# USBtoUART.net
KiCad netlist of a schematic drawn in Altium Designer
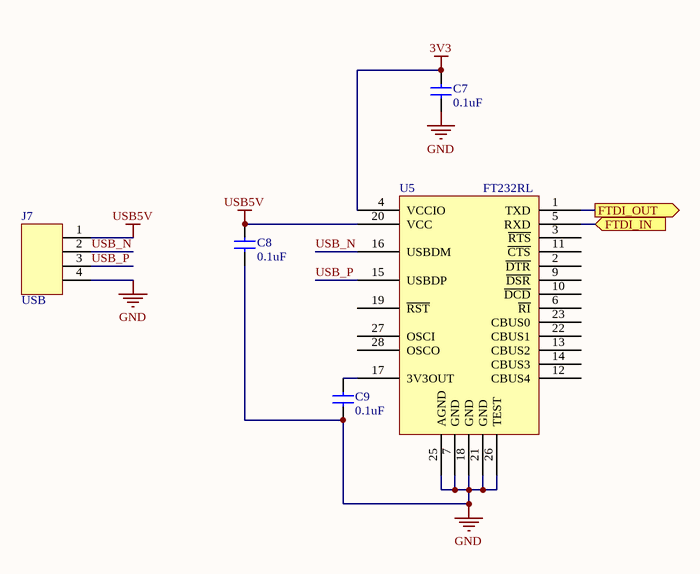
[diagram p0: USBtoUART.SchDoc]

(export (version "E")
  (design (tool "Eeschema 10.0.6"))
  (components
    (comp (ref "C7")
      (value "0.1uF")
      (footprint "CAPC0603")
      (fields (field (name "Comment") "Cap"))
      (libsource (lib "Passives") (part "Cap"))
    )
    (comp (ref "C8")
      (value "0.1uF")
      (footprint "CAPC0603")
      (fields (field (name "Comment") "Cap"))
      (libsource (lib "Passives") (part "Cap"))
    )
    (comp (ref "C9")
      (value "0.1uF")
      (footprint "CAPC0603")
      (fields (field (name "Comment") "Cap"))
      (libsource (lib "Passives") (part "Cap"))
    )
    (comp (ref "J7")
      (value "USB")
      (footprint "MOLEX-HDR-1X4-SHERLOCK-VERT")
      (libsource (lib "Connectors") (part "MOLEX-HDR-1x4-SHERLOCK_VERT"))
    )
    (comp (ref "U5")
      (value "FT232RL")
      (footprint "SSOP_28_N")
      (description "IC USB FS SERIAL UART 28-SSOP")
      (libsource (lib "ICs") (part "FT232RL"))
    )
  )
  (nets
    (net (code "1") (name "/FTDI_IN") (class "Default")
      (node (ref "U5") (pin "5") (pinfunction "RXD_5") (pintype "passive"))
    )
    (net (code "2") (name "/FTDI_OUT") (class "Default")
      (node (ref "U5") (pin "1") (pinfunction "TXD_1") (pintype "passive"))
    )
    (net (code "3") (name "/USB_N") (class "Default")
      (node (ref "J7") (pin "2") (pinfunction "2_2") (pintype "passive"))
      (node (ref "U5") (pin "16") (pinfunction "USBDM_16") (pintype "passive"))
    )
    (net (code "4") (name "/USB_P") (class "Default")
      (node (ref "J7") (pin "3") (pinfunction "3_3") (pintype "passive"))
      (node (ref "U5") (pin "15") (pinfunction "USBDP_15") (pintype "passive"))
    )
    (net (code "5") (name "3V3") (class "Default")
      (node (ref "C7") (pin "1") (pinfunction "A_1") (pintype "passive"))
      (node (ref "U5") (pin "4") (pinfunction "VCCIO_4") (pintype "passive"))
    )
    (net (code "6") (name "GND") (class "Default")
      (node (ref "C7") (pin "2") (pinfunction "B_2") (pintype "passive"))
      (node (ref "C8") (pin "2") (pinfunction "B_2") (pintype "passive"))
      (node (ref "C9") (pin "2") (pinfunction "B_2") (pintype "passive"))
      (node (ref "J7") (pin "4") (pinfunction "4_4") (pintype "passive"))
      (node (ref "U5") (pin "18") (pinfunction "GND_18") (pintype "passive"))
      (node (ref "U5") (pin "21") (pinfunction "GND_21") (pintype "passive"))
      (node (ref "U5") (pin "25") (pinfunction "AGND_25") (pintype "passive"))
      (node (ref "U5") (pin "26") (pinfunction "TEST_26") (pintype "passive"))
      (node (ref "U5") (pin "7") (pinfunction "GND_7") (pintype "passive"))
    )
    (net (code "7") (name "Net-(C9-A)") (class "Default")
      (node (ref "C9") (pin "1") (pinfunction "A_1") (pintype "passive"))
      (node (ref "U5") (pin "17") (pinfunction "3V3OUT_17") (pintype "passive"))
    )
    (net (code "8") (name "USB5V") (class "Default")
      (node (ref "C8") (pin "1") (pinfunction "A_1") (pintype "passive"))
      (node (ref "J7") (pin "1") (pinfunction "1_1") (pintype "passive"))
      (node (ref "U5") (pin "20") (pinfunction "VCC_20") (pintype "passive"))
    )
    (net (code "9") (name "unconnected-(U5-CBUS0-Pad23)") (class "Default")
      (node (ref "U5") (pin "23") (pinfunction "CBUS0_23") (pintype "passive"))
    )
    (net (code "10") (name "unconnected-(U5-CBUS1-Pad22)") (class "Default")
      (node (ref "U5") (pin "22") (pinfunction "CBUS1_22") (pintype "passive"))
    )
    (net (code "11") (name "unconnected-(U5-CBUS2-Pad13)") (class "Default")
      (node (ref "U5") (pin "13") (pinfunction "CBUS2_13") (pintype "passive"))
    )
    (net (code "12") (name "unconnected-(U5-CBUS3-Pad14)") (class "Default")
      (node (ref "U5") (pin "14") (pinfunction "CBUS3_14") (pintype "passive"))
    )
    (net (code "13") (name "unconnected-(U5-CBUS4-Pad12)") (class "Default")
      (node (ref "U5") (pin "12") (pinfunction "CBUS4_12") (pintype "passive"))
    )
    (net (code "14") (name "unconnected-(U5-OSCI-Pad27)") (class "Default")
      (node (ref "U5") (pin "27") (pinfunction "OSCI_27") (pintype "passive"))
    )
    (net (code "15") (name "unconnected-(U5-OSCO-Pad28)") (class "Default")
      (node (ref "U5") (pin "28") (pinfunction "OSCO_28") (pintype "passive"))
    )
    (net (code "16") (name "unconnected-(U5-~{CTS}-Pad11)") (class "Default")
      (node (ref "U5") (pin "11") (pinfunction "~{CTS}_11") (pintype "passive"))
    )
    (net (code "17") (name "unconnected-(U5-~{DCD}-Pad10)") (class "Default")
      (node (ref "U5") (pin "10") (pinfunction "~{DCD}_10") (pintype "passive"))
    )
    (net (code "18") (name "unconnected-(U5-~{DSR}-Pad9)") (class "Default")
      (node (ref "U5") (pin "9") (pinfunction "~{DSR}_9") (pintype "passive"))
    )
    (net (code "19") (name "unconnected-(U5-~{DTR}-Pad2)") (class "Default")
      (node (ref "U5") (pin "2") (pinfunction "~{DTR}_2") (pintype "passive"))
    )
    (net (code "20") (name "unconnected-(U5-~{RI}-Pad6)") (class "Default")
      (node (ref "U5") (pin "6") (pinfunction "~{RI}_6") (pintype "passive"))
    )
    (net (code "21") (name "unconnected-(U5-~{RST}-Pad19)") (class "Default")
      (node (ref "U5") (pin "19") (pinfunction "~{RST}_19") (pintype "passive"))
    )
    (net (code "22") (name "unconnected-(U5-~{RTS}-Pad3)") (class "Default")
      (node (ref "U5") (pin "3") (pinfunction "~{RTS}_3") (pintype "passive"))
    )
  )
)
